# WCH-Link.net
KiCad netlist of a schematic drawn in EasyEDA Pro
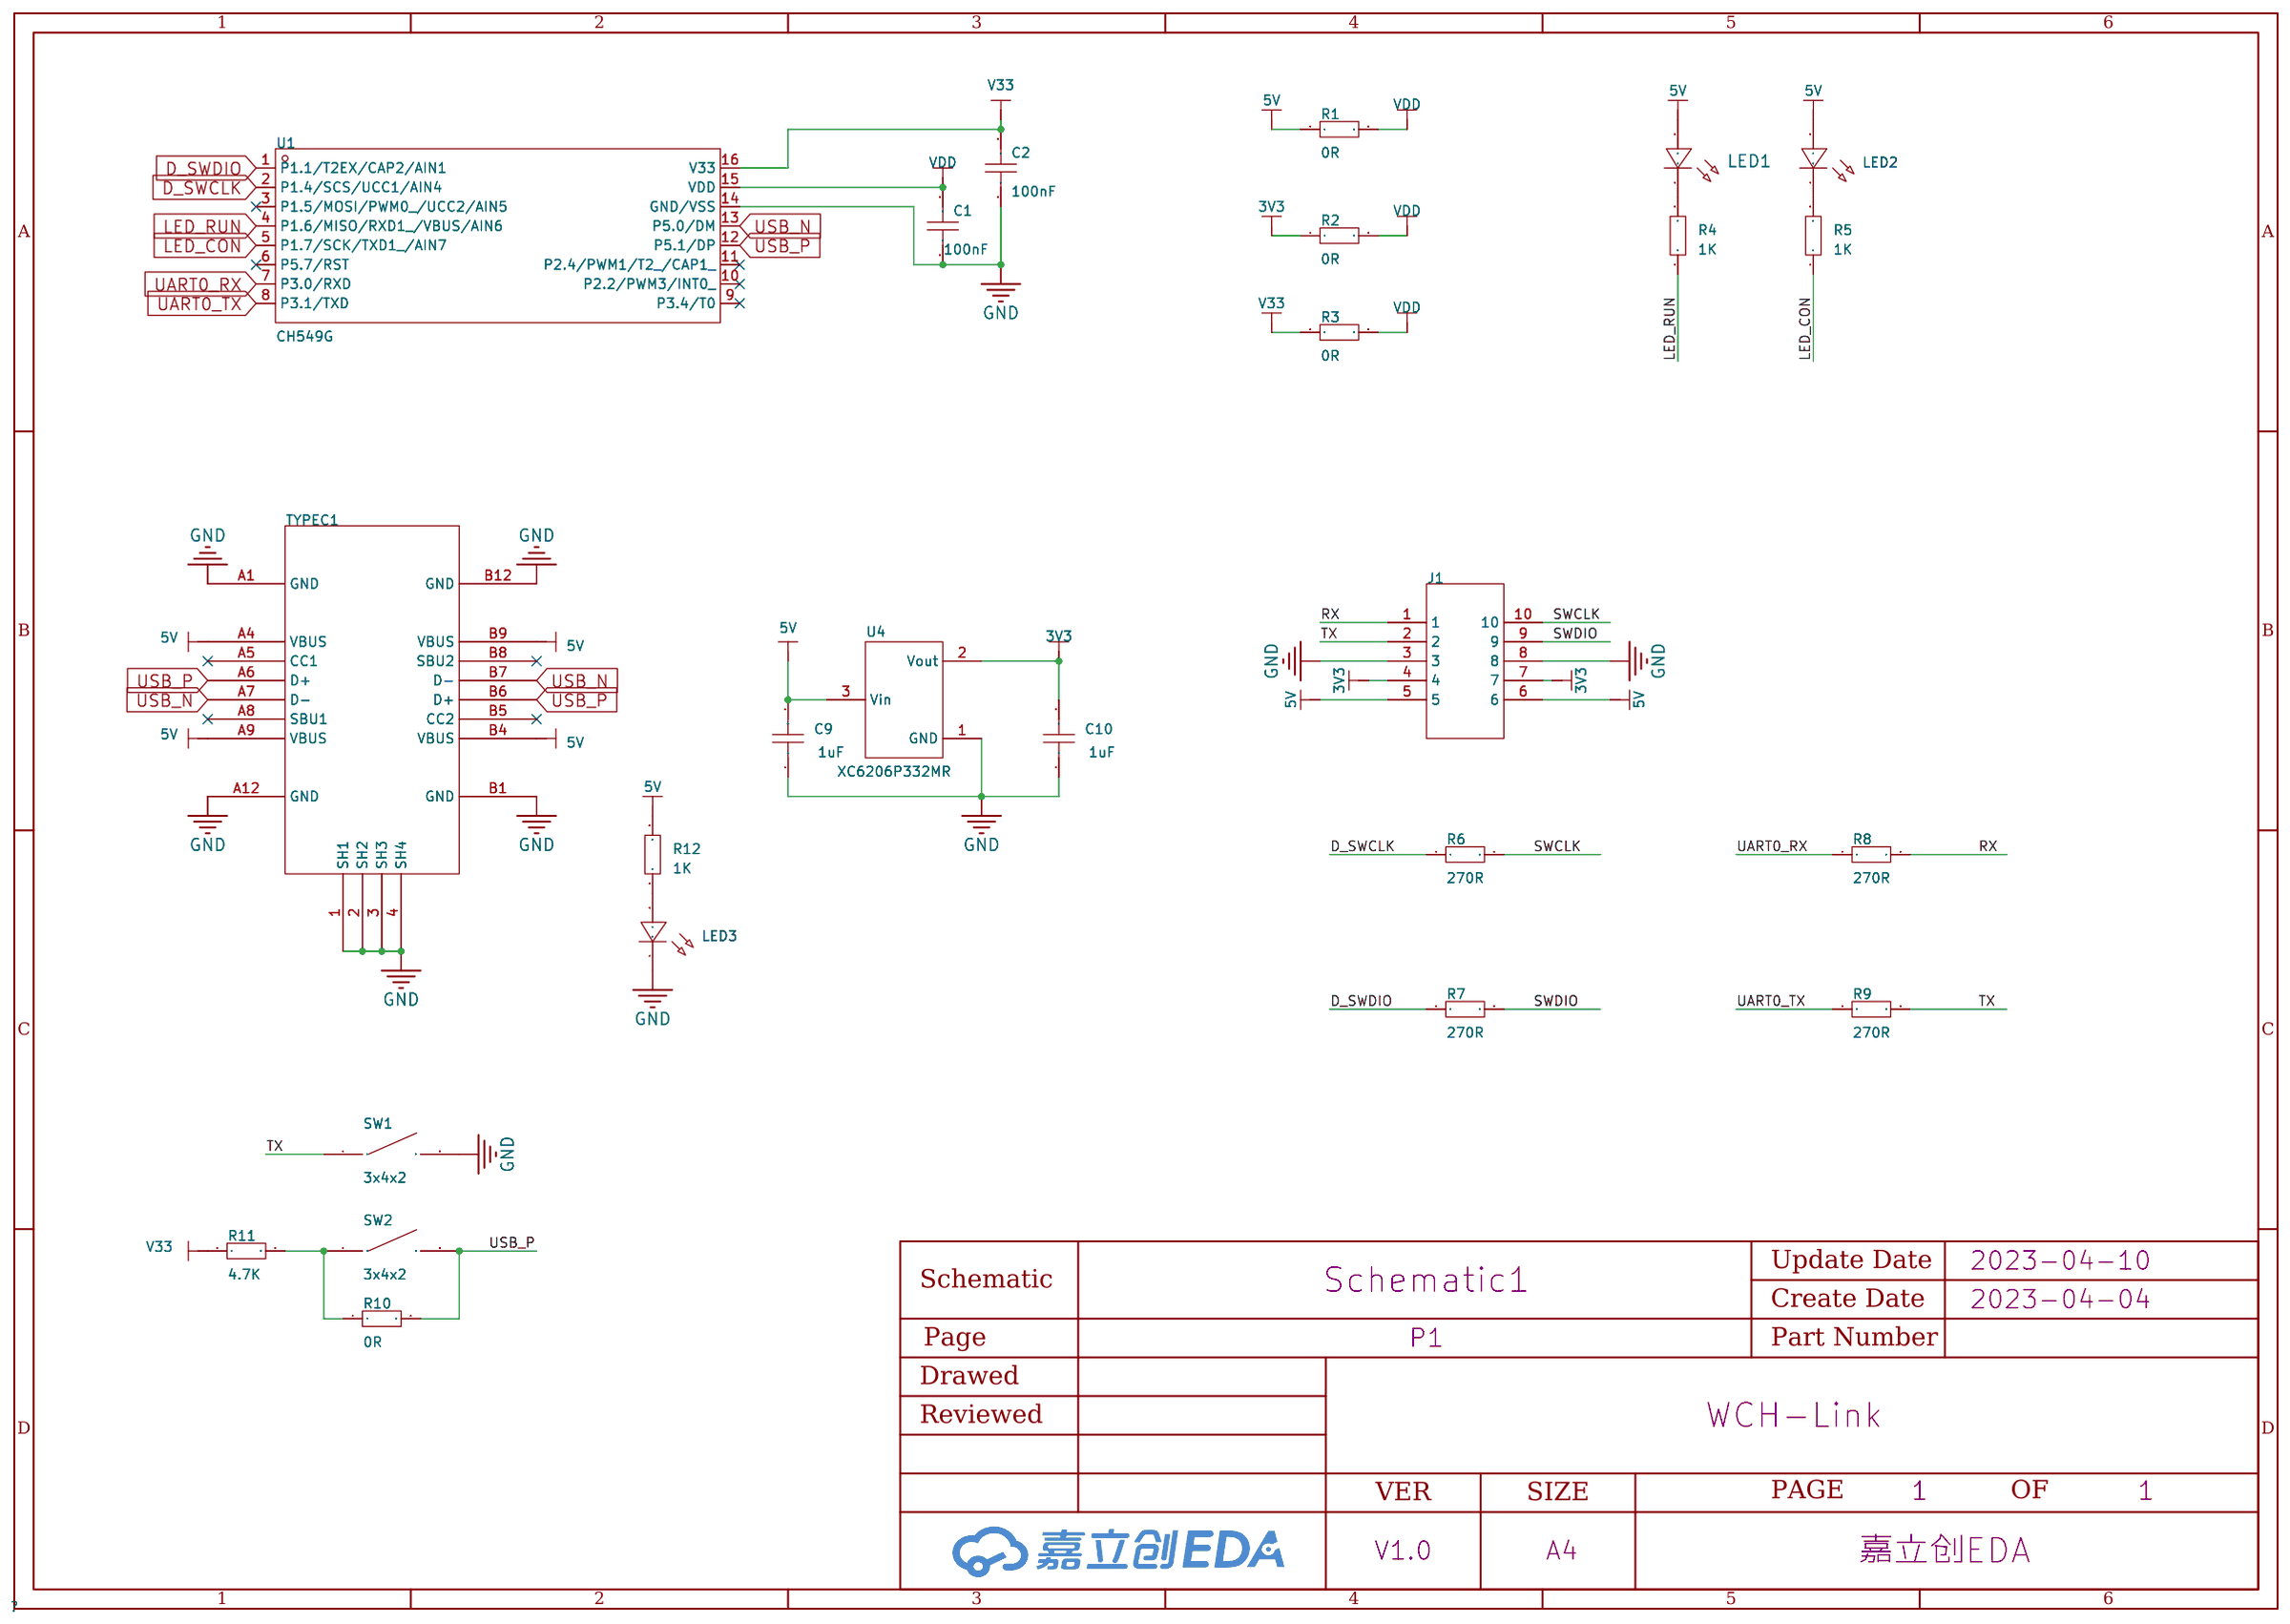
[diagram p0: schematic sheet]

(export (version "E")
  (design (tool "Eeschema 10.0.6"))
  (components
    (comp (ref "C1")
      (value "100nF")
      (footprint "easyedapro:C0603")
      (libsource (lib "easyedapro") (part "CapAcitance"))
    )
    (comp (ref "C2")
      (value "100nF")
      (footprint "easyedapro:C0603")
      (libsource (lib "easyedapro") (part "CapAcitance"))
    )
    (comp (ref "C9")
      (value "1uF")
      (footprint "easyedapro:C0603")
      (libsource (lib "easyedapro") (part "CapAcitance"))
    )
    (comp (ref "C10")
      (value "1uF")
      (footprint "easyedapro:C0603")
      (libsource (lib "easyedapro") (part "CapAcitance"))
    )
    (comp (ref "J1")
      (value "~")
      (footprint "easyedapro:WCH-link-J")
      (libsource (lib "easyedapro") (part "WCH-link-J"))
    )
    (comp (ref "LED1")
      (value "~")
      (footprint "easyedapro:LED_0805")
      (libsource (lib "easyedapro") (part "LED_R"))
    )
    (comp (ref "LED2")
      (value "~")
      (footprint "easyedapro:LED_0805")
      (libsource (lib "easyedapro") (part "LED_B"))
    )
    (comp (ref "LED3")
      (value "~")
      (footprint "easyedapro:LED_0805")
      (libsource (lib "easyedapro") (part "LED_G"))
    )
    (comp (ref "R1") (value "0R") (footprint "easyedapro:R0603") (libsource (lib "easyedapro") (part "电阻")))
    (comp (ref "R2") (value "0R") (footprint "easyedapro:R0603") (libsource (lib "easyedapro") (part "电阻")))
    (comp (ref "R3") (value "0R") (footprint "easyedapro:R0603") (libsource (lib "easyedapro") (part "电阻")))
    (comp (ref "R4") (value "1K") (footprint "easyedapro:R0603") (libsource (lib "easyedapro") (part "电阻")))
    (comp (ref "R5") (value "1K") (footprint "easyedapro:R0603") (libsource (lib "easyedapro") (part "电阻")))
    (comp (ref "R6") (value "270R") (footprint "easyedapro:R0603") (libsource (lib "easyedapro") (part "电阻")))
    (comp (ref "R7") (value "270R") (footprint "easyedapro:R0603") (libsource (lib "easyedapro") (part "电阻")))
    (comp (ref "R8") (value "270R") (footprint "easyedapro:R0603") (libsource (lib "easyedapro") (part "电阻")))
    (comp (ref "R9") (value "270R") (footprint "easyedapro:R0603") (libsource (lib "easyedapro") (part "电阻")))
    (comp (ref "R10") (value "0R") (footprint "easyedapro:R0603") (libsource (lib "easyedapro") (part "电阻")))
    (comp (ref "R11")
      (value "4.7K")
      (footprint "easyedapro:R0603")
      (libsource (lib "easyedapro") (part "电阻"))
    )
    (comp (ref "R12") (value "1K") (footprint "easyedapro:R0603") (libsource (lib "easyedapro") (part "电阻")))
    (comp (ref "SW1")
      (value "3x4x2")
      (footprint "easyedapro:SW-SMD_L4.0-W2.9-LS5.0")
      (fields
        (field (name "Manufacturer Part") "TS-1185-C-A-B-B")
        (field (name "Manufacturer") "XKB Connectivity(中国星坤)")
      )
      (libsource (lib "easyedapro") (part "TS-1185-C-A-B-B"))
    )
    (comp (ref "SW2")
      (value "3x4x2")
      (footprint "easyedapro:SW-SMD_L4.0-W2.9-LS5.0")
      (fields
        (field (name "Manufacturer Part") "TS-1185-C-A-B-B")
        (field (name "Manufacturer") "XKB Connectivity(中国星坤)")
      )
      (libsource (lib "easyedapro") (part "TS-1185-C-A-B-B"))
    )
    (comp (ref "TYPEC1")
      (value "~")
      (footprint "easyedapro:TypeC-16p")
      (libsource (lib "easyedapro") (part "Type C"))
    )
    (comp (ref "U1")
      (value "CH549G")
      (footprint "easyedapro:SOP-16_L10.0-W3.9-P1.27-LS6.0-BL")
      (libsource (lib "easyedapro") (part "CH549G"))
    )
    (comp (ref "U4")
      (value "XC6206P332MR")
      (footprint "easyedapro:SOT-23-3_L2.9-W1.6-P1.90-LS2.8-BR")
      (description "输出类型:固定;输出极性:正;输出通道数:1;最大输入电压:6V;输出电压:3.3V;压差:680mV@(100mA);输出电流:200mA;电源纹波抑制比(PRSS):-;")
      (fields (field (name "Manufacturer") "TOREX(特瑞仕)"))
      (libsource (lib "easyedapro") (part "XC6206P332MR"))
    )
  )
  (nets
    (net (code "1") (name "/RX") (class "Default")
      (node (ref "J1") (pin "1") (pinfunction "1_1") (pintype "input"))
      (node (ref "R8") (pin "2") (pinfunction "2_2") (pintype "input"))
    )
    (net (code "2") (name "/SWCLK") (class "Default")
      (node (ref "J1") (pin "10") (pinfunction "10_10") (pintype "input"))
      (node (ref "R6") (pin "2") (pinfunction "2_2") (pintype "input"))
    )
    (net (code "3") (name "/SWDIO") (class "Default")
      (node (ref "J1") (pin "9") (pinfunction "9_9") (pintype "input"))
      (node (ref "R7") (pin "2") (pinfunction "2_2") (pintype "input"))
    )
    (net (code "4") (name "/TX") (class "Default")
      (node (ref "J1") (pin "2") (pinfunction "2_2") (pintype "input"))
      (node (ref "R9") (pin "2") (pinfunction "2_2") (pintype "input"))
      (node (ref "SW1") (pin "1") (pinfunction "1_1") (pintype "input"))
    )
    (net (code "5") (name "3V3") (class "Default")
      (node (ref "C10") (pin "2") (pinfunction "2_2") (pintype "input"))
      (node (ref "J1") (pin "4") (pinfunction "4_4") (pintype "input"))
      (node (ref "J1") (pin "7") (pinfunction "7_7") (pintype "input"))
      (node (ref "R2") (pin "1") (pinfunction "1_1") (pintype "input"))
      (node (ref "U4") (pin "2") (pinfunction "Vout_2") (pintype "input"))
    )
    (net (code "6") (name "5V") (class "Default")
      (node (ref "C9") (pin "2") (pinfunction "2_2") (pintype "input"))
      (node (ref "J1") (pin "5") (pinfunction "5_5") (pintype "input"))
      (node (ref "J1") (pin "6") (pinfunction "6_6") (pintype "input"))
      (node (ref "LED1") (pin "2") (pinfunction "A_2") (pintype "input"))
      (node (ref "LED2") (pin "2") (pinfunction "A_2") (pintype "input"))
      (node (ref "R1") (pin "1") (pinfunction "1_1") (pintype "input"))
      (node (ref "R12") (pin "2") (pinfunction "2_2") (pintype "input"))
      (node (ref "TYPEC1") (pin "A4") (pinfunction "VBUS_A4") (pintype "input"))
      (node (ref "TYPEC1") (pin "A9") (pinfunction "VBUS_A9") (pintype "input"))
      (node (ref "TYPEC1") (pin "B4") (pinfunction "VBUS_B4") (pintype "input"))
      (node (ref "TYPEC1") (pin "B9") (pinfunction "VBUS_B9") (pintype "input"))
      (node (ref "U4") (pin "3") (pinfunction "Vin_3") (pintype "input"))
    )
    (net (code "7") (name "D_SWCLK") (class "Default")
      (node (ref "R6") (pin "1") (pinfunction "1_1") (pintype "input"))
      (node (ref "U1") (pin "2") (pinfunction "P1.4/SCS/UCC1/AIN4_2") (pintype "input"))
    )
    (net (code "8") (name "D_SWDIO") (class "Default")
      (node (ref "R7") (pin "1") (pinfunction "1_1") (pintype "input"))
      (node (ref "U1") (pin "1") (pinfunction "P1.1/T2EX/CAP2/AIN1_1") (pintype "input"))
    )
    (net (code "9") (name "GND") (class "Default")
      (node (ref "C1") (pin "1") (pinfunction "1_1") (pintype "input"))
      (node (ref "C10") (pin "1") (pinfunction "1_1") (pintype "input"))
      (node (ref "C2") (pin "1") (pinfunction "1_1") (pintype "input"))
      (node (ref "C9") (pin "1") (pinfunction "1_1") (pintype "input"))
      (node (ref "J1") (pin "3") (pinfunction "3_3") (pintype "input"))
      (node (ref "J1") (pin "8") (pinfunction "8_8") (pintype "input"))
      (node (ref "LED3") (pin "1") (pinfunction "C_1") (pintype "input"))
      (node (ref "SW1") (pin "2") (pinfunction "2_2") (pintype "input"))
      (node (ref "TYPEC1") (pin "1") (pinfunction "SH1_1") (pintype "input"))
      (node (ref "TYPEC1") (pin "2") (pinfunction "SH2_2") (pintype "input"))
      (node (ref "TYPEC1") (pin "3") (pinfunction "SH3_3") (pintype "input"))
      (node (ref "TYPEC1") (pin "4") (pinfunction "SH4_4") (pintype "input"))
      (node (ref "TYPEC1") (pin "A1") (pinfunction "GND_A1") (pintype "input"))
      (node (ref "TYPEC1") (pin "A12") (pinfunction "GND_A12") (pintype "input"))
      (node (ref "TYPEC1") (pin "B1") (pinfunction "GND_B1") (pintype "input"))
      (node (ref "TYPEC1") (pin "B12") (pinfunction "GND_B12") (pintype "input"))
      (node (ref "U1") (pin "14") (pinfunction "GND/VSS_14") (pintype "input"))
      (node (ref "U4") (pin "1") (pinfunction "GND_1") (pintype "input"))
    )
    (net (code "10") (name "LED_CON") (class "Default")
      (node (ref "R5") (pin "1") (pinfunction "1_1") (pintype "input"))
      (node (ref "U1") (pin "5") (pinfunction "P1.7/SCK/TXD1_/AIN7_5") (pintype "input"))
    )
    (net (code "11") (name "LED_RUN") (class "Default")
      (node (ref "R4") (pin "1") (pinfunction "1_1") (pintype "input"))
      (node (ref "U1") (pin "4") (pinfunction "P1.6/MISO/RXD1_/VBUS/AIN6_4") (pintype "input"))
    )
    (net (code "12") (name "Net-(LED1-C)") (class "Default")
      (node (ref "LED1") (pin "1") (pinfunction "C_1") (pintype "input"))
      (node (ref "R4") (pin "2") (pinfunction "2_2") (pintype "input"))
    )
    (net (code "13") (name "Net-(LED2-C)") (class "Default")
      (node (ref "LED2") (pin "1") (pinfunction "C_1") (pintype "input"))
      (node (ref "R5") (pin "2") (pinfunction "2_2") (pintype "input"))
    )
    (net (code "14") (name "Net-(LED3-A)") (class "Default")
      (node (ref "LED3") (pin "2") (pinfunction "A_2") (pintype "input"))
      (node (ref "R12") (pin "1") (pinfunction "1_1") (pintype "input"))
    )
    (net (code "15") (name "Net-(R10-Pad1)") (class "Default")
      (node (ref "R10") (pin "1") (pinfunction "1_1") (pintype "input"))
      (node (ref "R11") (pin "2") (pinfunction "2_2") (pintype "input"))
      (node (ref "SW2") (pin "1") (pinfunction "1_1") (pintype "input"))
    )
    (net (code "16") (name "UART0_RX") (class "Default")
      (node (ref "R8") (pin "1") (pinfunction "1_1") (pintype "input"))
      (node (ref "U1") (pin "7") (pinfunction "P3.0/RXD_7") (pintype "input"))
    )
    (net (code "17") (name "UART0_TX") (class "Default")
      (node (ref "R9") (pin "1") (pinfunction "1_1") (pintype "input"))
      (node (ref "U1") (pin "8") (pinfunction "P3.1/TXD_8") (pintype "input"))
    )
    (net (code "18") (name "USB_N") (class "Default")
      (node (ref "TYPEC1") (pin "A7") (pinfunction "D-_A7") (pintype "input"))
      (node (ref "TYPEC1") (pin "B7") (pinfunction "D-_B7") (pintype "input"))
      (node (ref "U1") (pin "13") (pinfunction "P5.0/DM_13") (pintype "input"))
    )
    (net (code "19") (name "USB_P") (class "Default")
      (node (ref "R10") (pin "2") (pinfunction "2_2") (pintype "input"))
      (node (ref "SW2") (pin "2") (pinfunction "2_2") (pintype "input"))
      (node (ref "TYPEC1") (pin "A6") (pinfunction "D+_A6") (pintype "input"))
      (node (ref "TYPEC1") (pin "B6") (pinfunction "D+_B6") (pintype "input"))
      (node (ref "U1") (pin "12") (pinfunction "P5.1/DP_12") (pintype "input"))
    )
    (net (code "20") (name "V33") (class "Default")
      (node (ref "C2") (pin "2") (pinfunction "2_2") (pintype "input"))
      (node (ref "R11") (pin "1") (pinfunction "1_1") (pintype "input"))
      (node (ref "R3") (pin "1") (pinfunction "1_1") (pintype "input"))
      (node (ref "U1") (pin "16") (pinfunction "V33_16") (pintype "input"))
    )
    (net (code "21") (name "VDD") (class "Default")
      (node (ref "C1") (pin "2") (pinfunction "2_2") (pintype "input"))
      (node (ref "R1") (pin "2") (pinfunction "2_2") (pintype "input"))
      (node (ref "R2") (pin "2") (pinfunction "2_2") (pintype "input"))
      (node (ref "R3") (pin "2") (pinfunction "2_2") (pintype "input"))
      (node (ref "U1") (pin "15") (pinfunction "VDD_15") (pintype "input"))
    )
    (net (code "22") (name "unconnected-(TYPEC1-CC1-PadA5)") (class "Default")
      (node (ref "TYPEC1") (pin "A5") (pinfunction "CC1_A5") (pintype "input+no_connect"))
    )
    (net (code "23") (name "unconnected-(TYPEC1-CC2-PadB5)") (class "Default")
      (node (ref "TYPEC1") (pin "B5") (pinfunction "CC2_B5") (pintype "input+no_connect"))
    )
    (net (code "24") (name "unconnected-(TYPEC1-SBU1-PadA8)") (class "Default")
      (node (ref "TYPEC1") (pin "A8") (pinfunction "SBU1_A8") (pintype "input+no_connect"))
    )
    (net (code "25") (name "unconnected-(TYPEC1-SBU2-PadB8)") (class "Default")
      (node (ref "TYPEC1") (pin "B8") (pinfunction "SBU2_B8") (pintype "input+no_connect"))
    )
    (net (code "26") (name "unconnected-(U1-P1.5{slash}MOSI{slash}PWM0_{slash}UCC2{slash}AIN5-Pad3)") (class "Default")
      (node (ref "U1") (pin "3") (pinfunction "P1.5/MOSI/PWM0_/UCC2/AIN5_3") (pintype "input+no_connect"))
    )
    (net (code "27") (name "unconnected-(U1-P2.2{slash}PWM3{slash}INT0_-Pad10)") (class "Default")
      (node (ref "U1") (pin "10") (pinfunction "P2.2/PWM3/INT0__10") (pintype "input+no_connect"))
    )
    (net (code "28") (name "unconnected-(U1-P2.4{slash}PWM1{slash}T2_{slash}CAP1_-Pad11)") (class "Default")
      (node (ref "U1") (pin "11") (pinfunction "P2.4/PWM1/T2_/CAP1__11") (pintype "input+no_connect"))
    )
    (net (code "29") (name "unconnected-(U1-P3.4{slash}T0-Pad9)") (class "Default")
      (node (ref "U1") (pin "9") (pinfunction "P3.4/T0_9") (pintype "input+no_connect"))
    )
    (net (code "30") (name "unconnected-(U1-P5.7{slash}RST-Pad6)") (class "Default")
      (node (ref "U1") (pin "6") (pinfunction "P5.7/RST_6") (pintype "input+no_connect"))
    )
  )
)
